# Schematic.net
KiCad netlist of a schematic drawn in EasyEDA
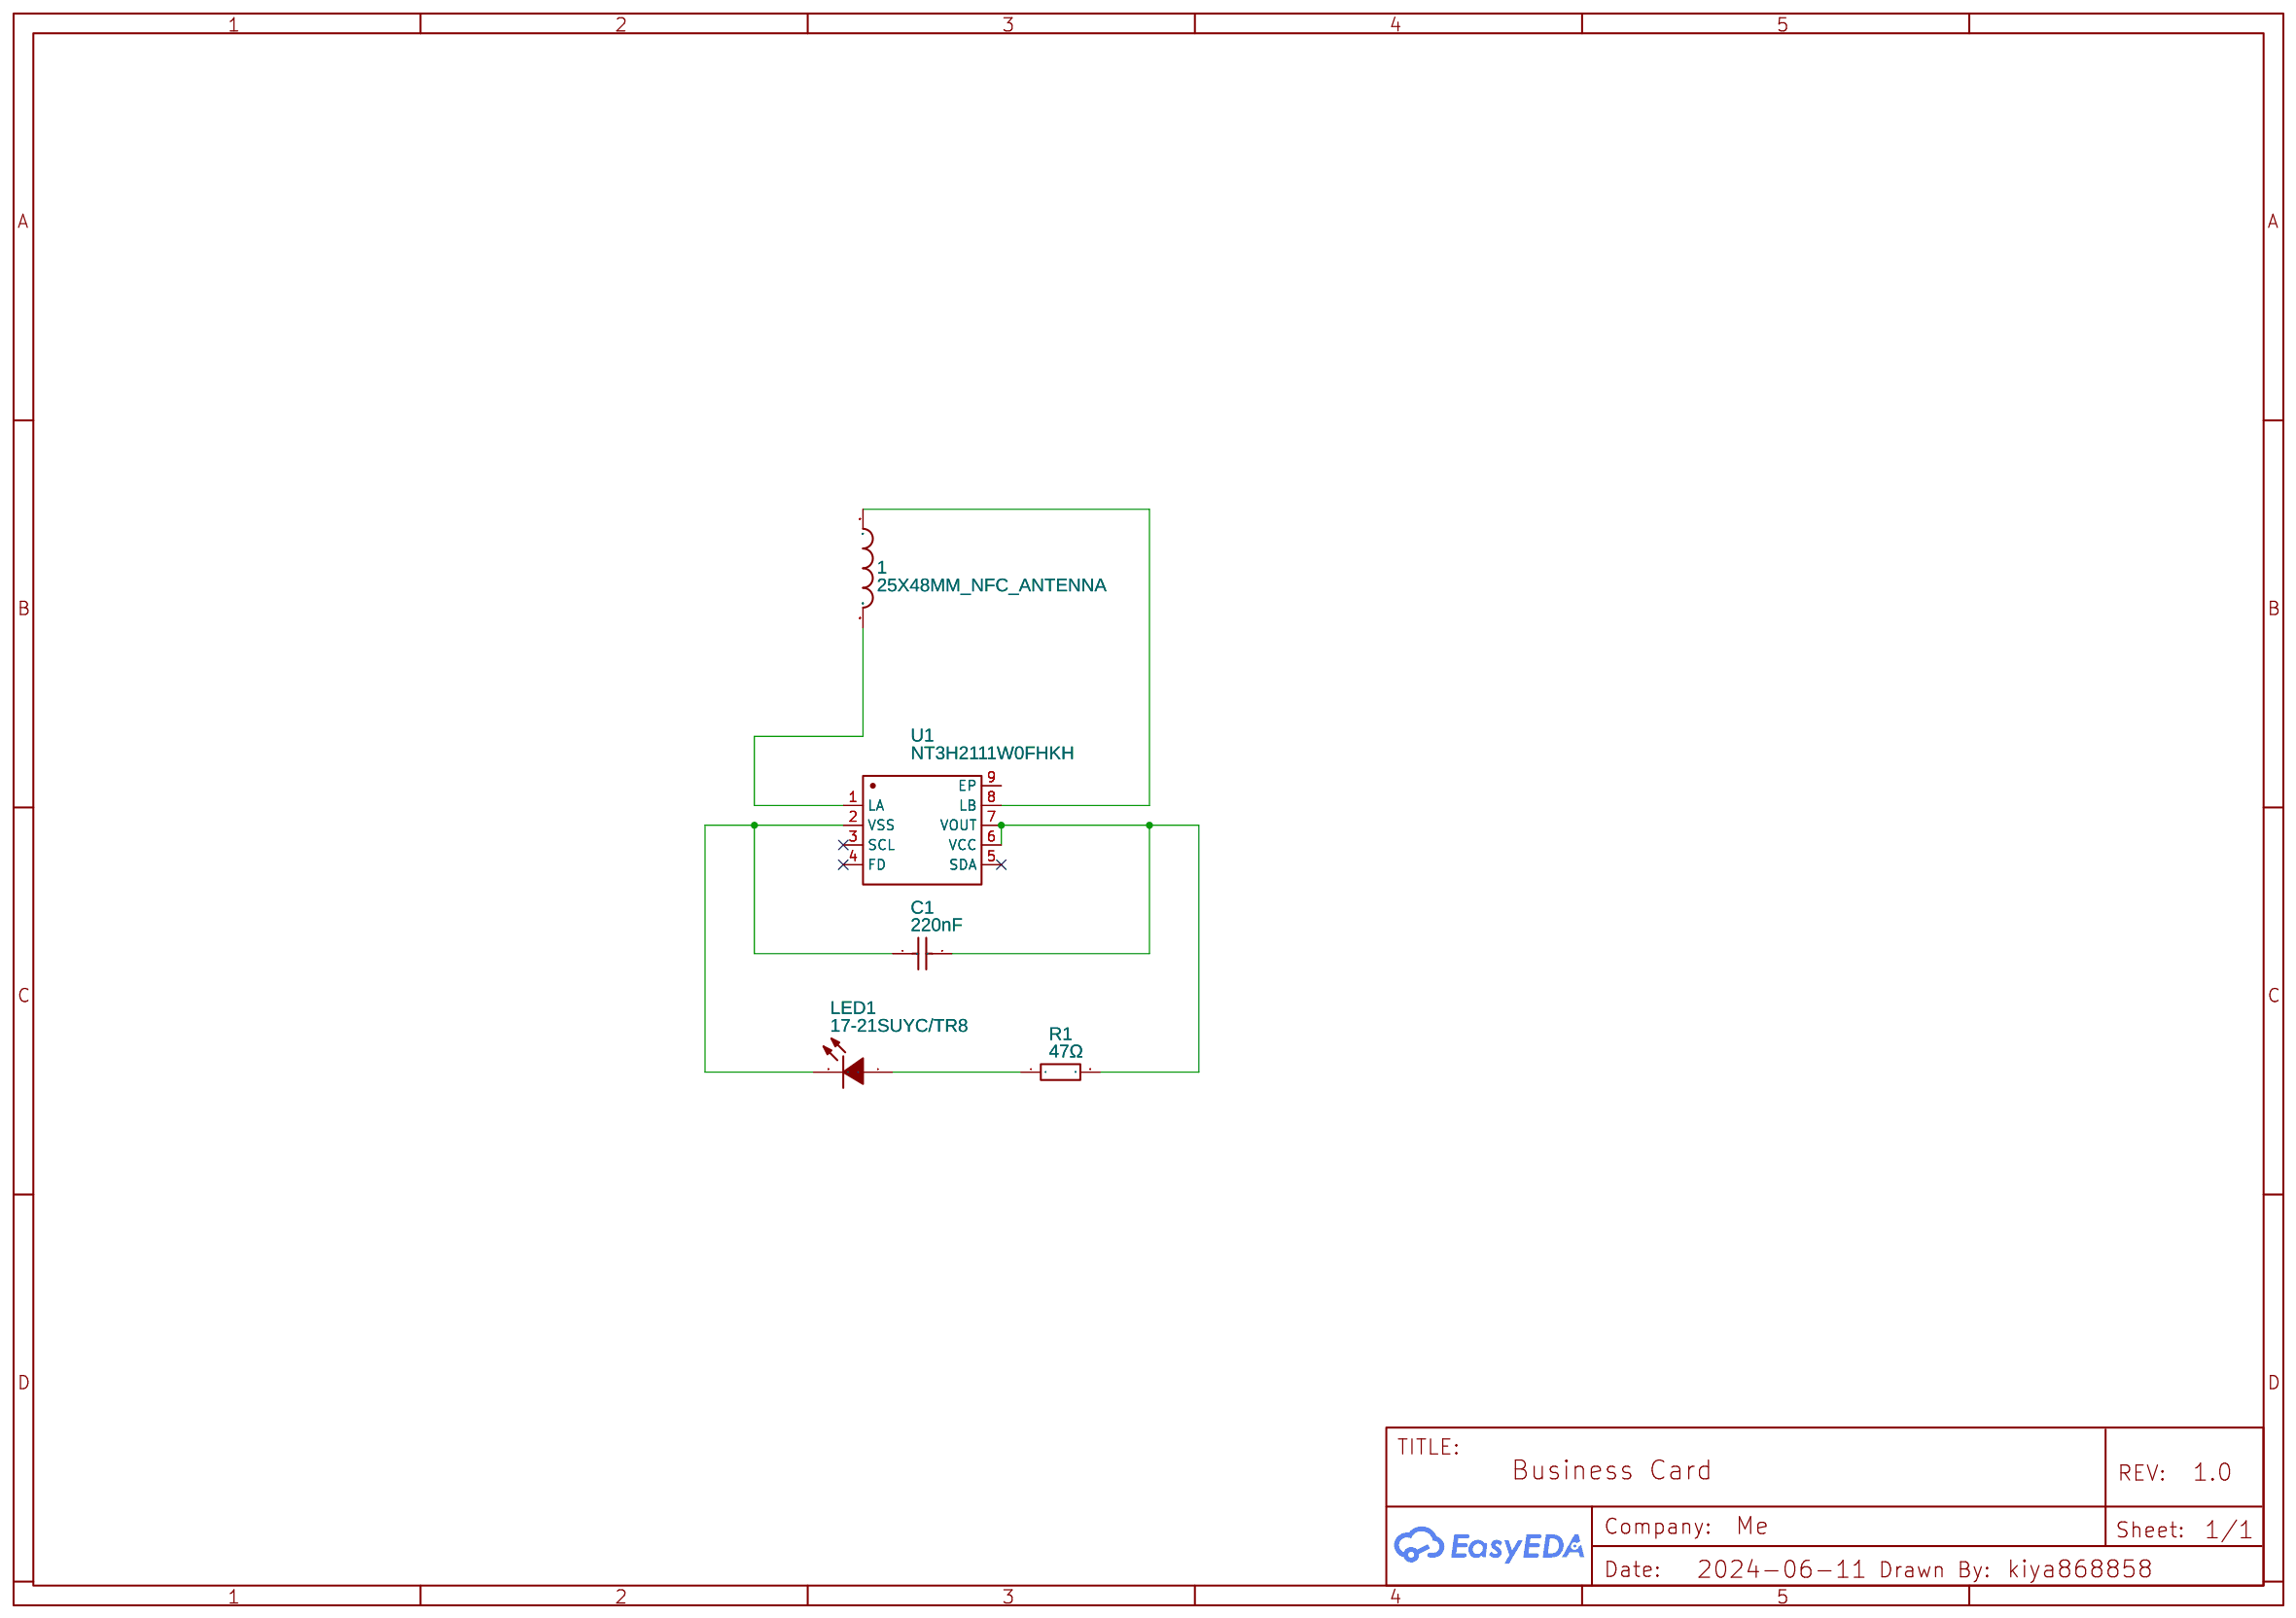
[diagram p0: schematic sheet]

(export (version "E")
  (design (tool "Eeschema 10.0.6"))
  (components
    (comp (ref "1") (value "25X48MM_NFC_ANTENNA") (libsource (lib "") (part "25X48MM_NFC_ANTENNA")))
    (comp (ref "C1")
      (value "220nF")
      (fields
        (field (name "Manufacturer Part") "CL10B224KA8NNNC")
        (field (name "Manufacturer") "SAMSUNG(三星)")
      )
      (libsource (lib "") (part "CL10B224KA8NNNC"))
    )
    (comp (ref "LED1")
      (value "17-21SUYC/TR8")
      (fields (field (name "Manufacturer Part") "KT-0805黄灯") (field (name "Manufacturer") "KENTO"))
      (libsource (lib "") (part "17-21SUYC/TR8"))
    )
    (comp (ref "R1")
      (value "47Ω")
      (fields
        (field (name "Manufacturer Part") "0603WAF470JT5E")
        (field (name "Manufacturer") "UNI-ROYAL(厚声)")
      )
      (libsource (lib "") (part "0603WAF470JT5E"))
    )
    (comp (ref "U1")
      (value "NT3H2111W0FHKH")
      (fields (field (name "Manufacturer") "NXP(恩智浦)"))
      (libsource (lib "") (part "NT3H2111W0FHKH"))
    )
  )
  (nets
    (net (code "1") (name "Net-(LED1-+)") (class "Default")
      (node (ref "LED1") (pin "1") (pinfunction "+_1") (pintype "unspecified"))
      (node (ref "R1") (pin "1") (pinfunction "1_1") (pintype "input"))
    )
    (net (code "2") (name "Net-(LED1--)") (class "Default")
      (node (ref "C1") (pin "1") (pinfunction "1_1") (pintype "input"))
      (node (ref "LED1") (pin "2") (pinfunction "-_2") (pintype "unspecified"))
      (node (ref "U1") (pin "2") (pinfunction "VSS_2") (pintype "unspecified"))
    )
    (net (code "3") (name "Net-(U1-LA)") (class "Default")
      (node (ref "1") (pin "P$2") (pinfunction "P$2_P$2") (pintype "bidirectional"))
      (node (ref "U1") (pin "1") (pinfunction "LA_1") (pintype "unspecified"))
    )
    (net (code "4") (name "Net-(U1-LB)") (class "Default")
      (node (ref "1") (pin "P$1") (pinfunction "P$1_P$1") (pintype "bidirectional"))
      (node (ref "U1") (pin "8") (pinfunction "LB_8") (pintype "unspecified"))
    )
    (net (code "5") (name "Net-(U1-VCC)") (class "Default")
      (node (ref "C1") (pin "2") (pinfunction "2_2") (pintype "input"))
      (node (ref "R1") (pin "2") (pinfunction "2_2") (pintype "input"))
      (node (ref "U1") (pin "6") (pinfunction "VCC_6") (pintype "unspecified"))
      (node (ref "U1") (pin "7") (pinfunction "VOUT_7") (pintype "unspecified"))
    )
    (net (code "6") (name "unconnected-(U1-EP-Pad9)") (class "Default")
      (node (ref "U1") (pin "9") (pinfunction "EP_9") (pintype "unspecified"))
    )
    (net (code "7") (name "unconnected-(U1-FD-Pad4)") (class "Default")
      (node (ref "U1") (pin "4") (pinfunction "FD_4") (pintype "unspecified+no_connect"))
    )
    (net (code "8") (name "unconnected-(U1-SCL-Pad3)") (class "Default")
      (node (ref "U1") (pin "3") (pinfunction "SCL_3") (pintype "unspecified+no_connect"))
    )
    (net (code "9") (name "unconnected-(U1-SDA-Pad5)") (class "Default")
      (node (ref "U1") (pin "5") (pinfunction "SDA_5") (pintype "unspecified+no_connect"))
    )
  )
)
